# schematic.net
KiCad netlist of a schematic drawn in EasyEDA
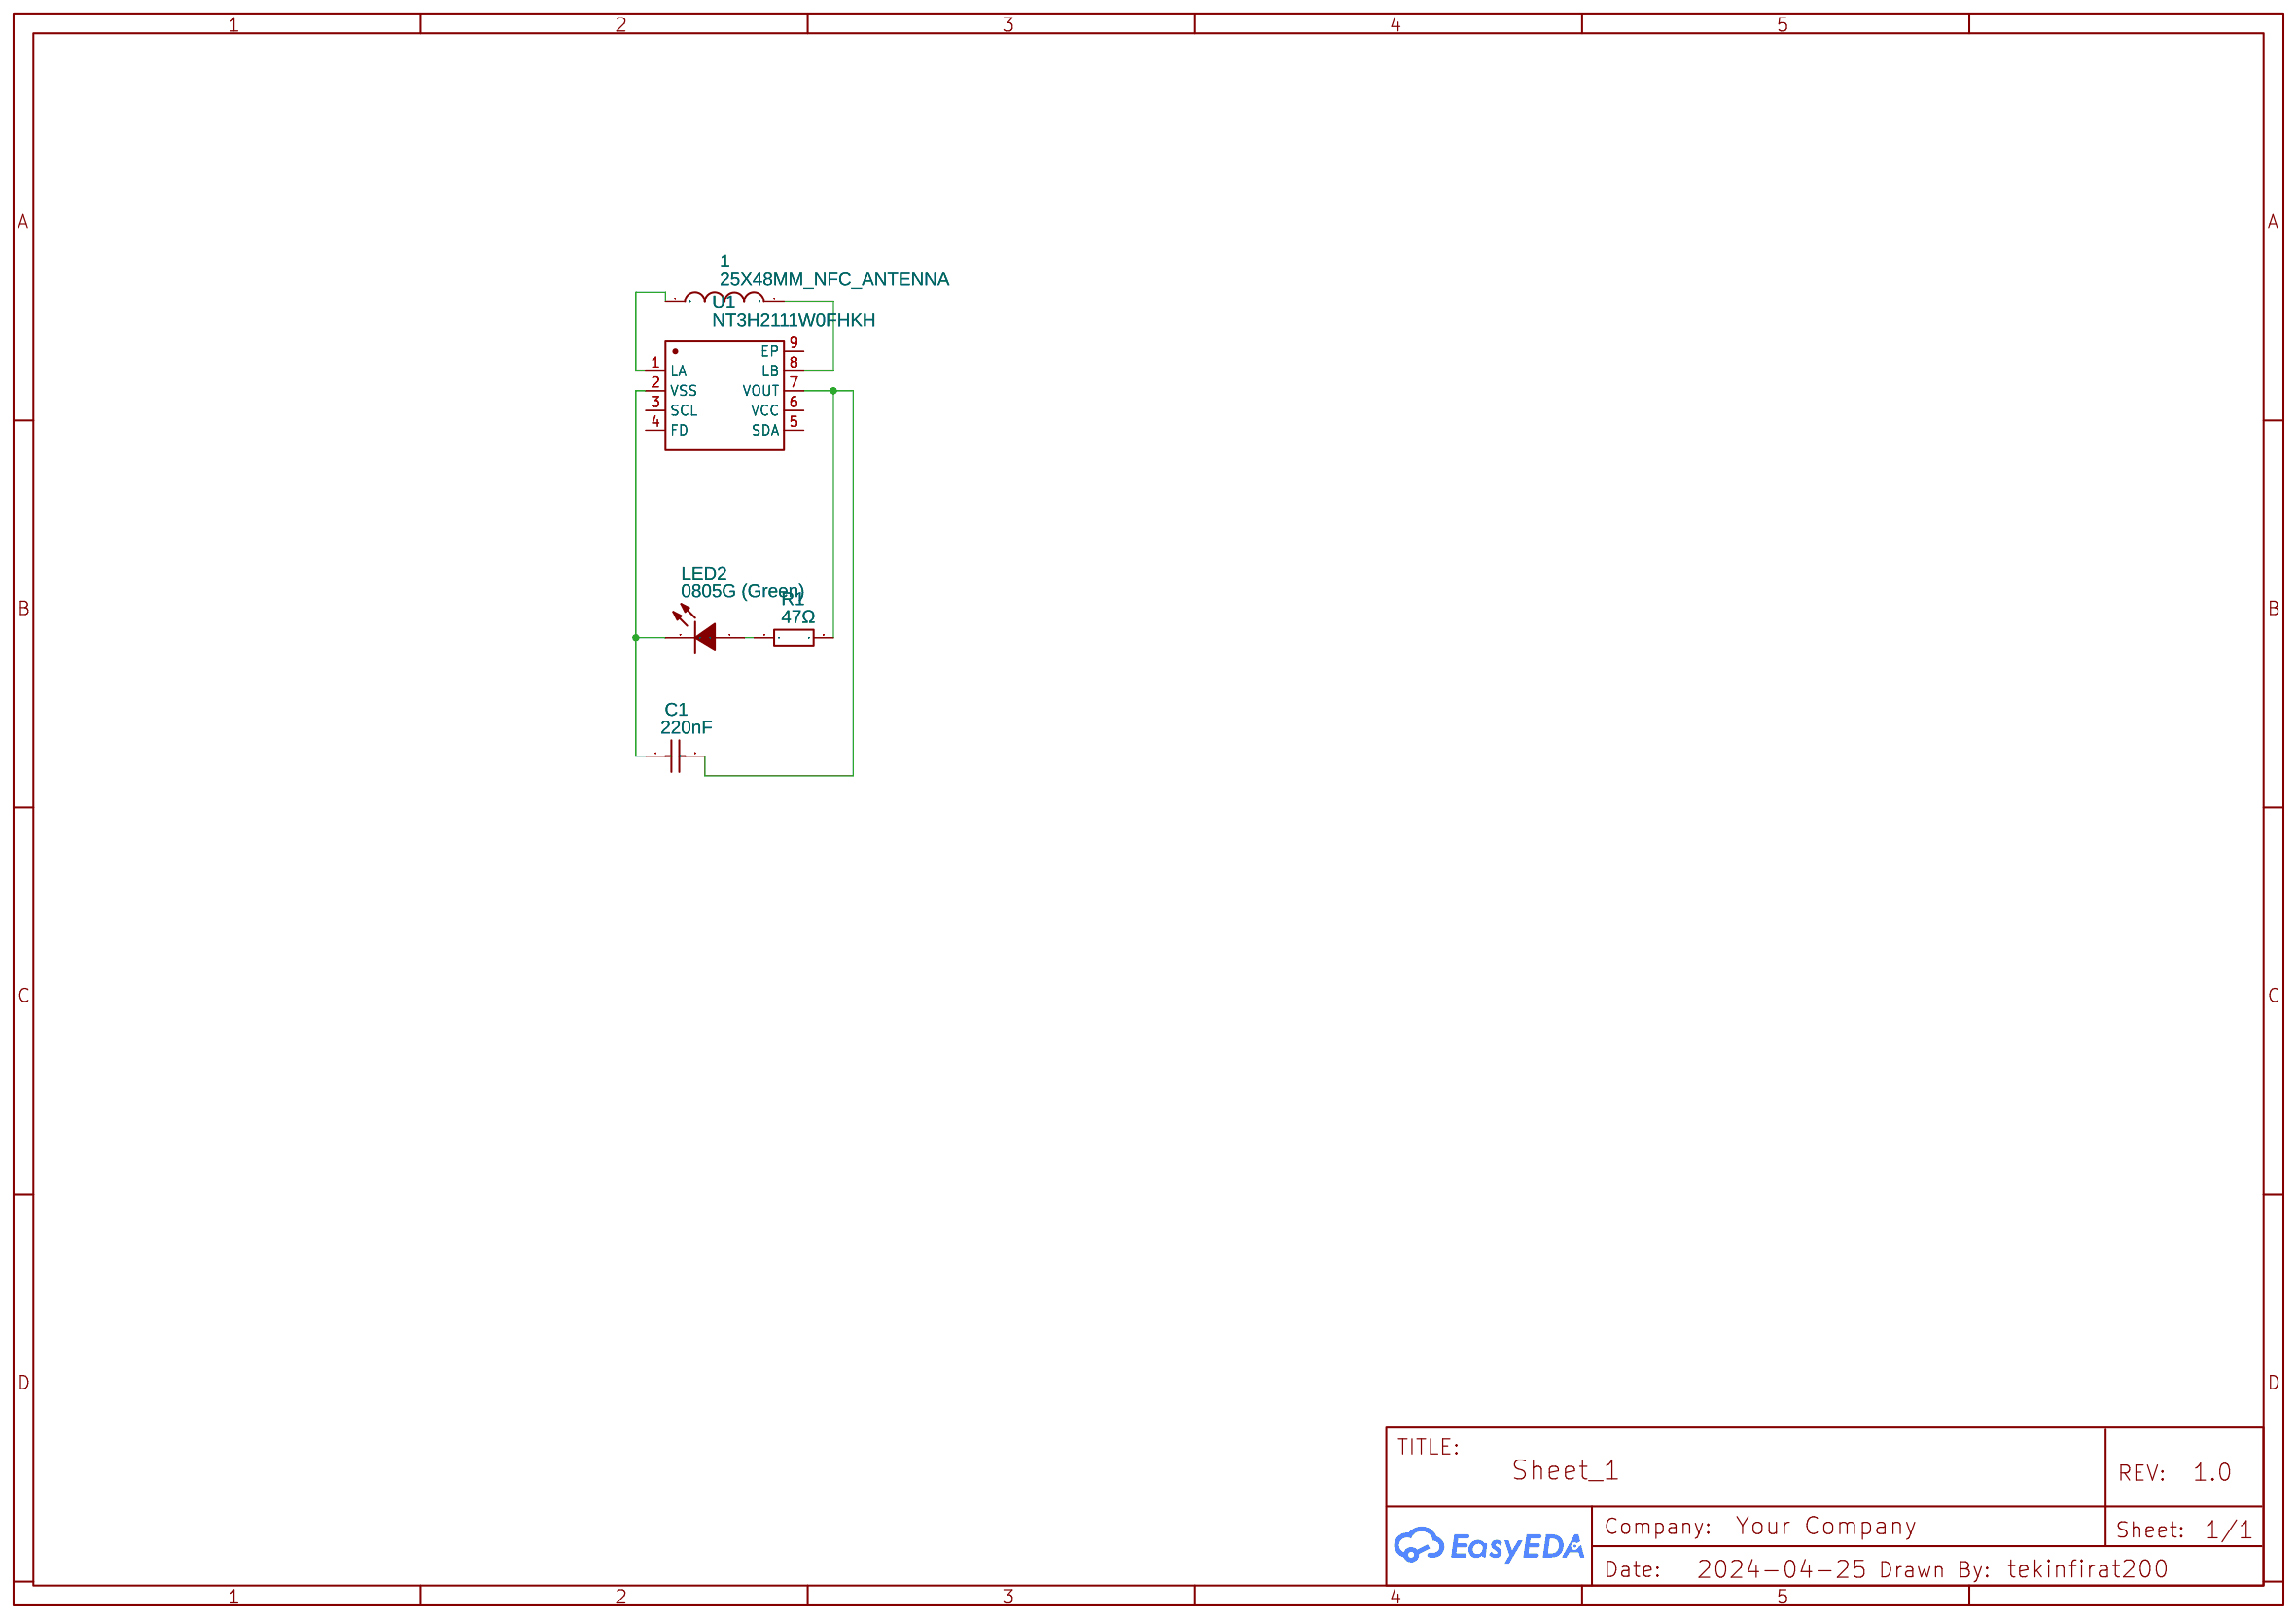
[diagram p0: schematic sheet]

(export (version "E")
  (design (tool "Eeschema 10.0.6"))
  (components
    (comp (ref "1") (value "25X48MM_NFC_ANTENNA") (libsource (lib "") (part "25X48MM_NFC_ANTENNA")))
    (comp (ref "C1")
      (value "220nF")
      (fields
        (field (name "Manufacturer Part") "CL10B224KA8NNNC")
        (field (name "Manufacturer") "SAMSUNG(三星)")
      )
      (libsource (lib "") (part "CL10B224KA8NNNC"))
    )
    (comp (ref "LED2")
      (value "0805G (Green)")
      (fields (field (name "Manufacturer Part") "KT-0805G") (field (name "Manufacturer") "KENTO"))
      (libsource (lib "") (part "0805G (Green)"))
    )
    (comp (ref "R1")
      (value "47Ω")
      (fields
        (field (name "Manufacturer Part") "0603WAF470JT5E")
        (field (name "Manufacturer") "UNI-ROYAL(厚声)")
      )
      (libsource (lib "") (part "0603WAF470JT5E"))
    )
    (comp (ref "U1")
      (value "NT3H2111W0FHKH")
      (fields (field (name "Manufacturer") "NXP(恩智浦)"))
      (libsource (lib "") (part "NT3H2111W0FHKH"))
    )
  )
  (nets
    (net (code "1") (name "Net-(LED2-A)") (class "Default")
      (node (ref "LED2") (pin "1") (pinfunction "A_1") (pintype "unspecified"))
      (node (ref "R1") (pin "1") (pinfunction "1_1") (pintype "input"))
    )
    (net (code "2") (name "Net-(LED2-K)") (class "Default")
      (node (ref "C1") (pin "1") (pinfunction "1_1") (pintype "input"))
      (node (ref "LED2") (pin "2") (pinfunction "K_2") (pintype "unspecified"))
      (node (ref "U1") (pin "2") (pinfunction "VSS_2") (pintype "unspecified"))
    )
    (net (code "3") (name "Net-(U1-LA)") (class "Default")
      (node (ref "1") (pin "P$1") (pinfunction "P$1_P$1") (pintype "bidirectional"))
      (node (ref "U1") (pin "1") (pinfunction "LA_1") (pintype "unspecified"))
    )
    (net (code "4") (name "Net-(U1-LB)") (class "Default")
      (node (ref "1") (pin "P$2") (pinfunction "P$2_P$2") (pintype "bidirectional"))
      (node (ref "U1") (pin "8") (pinfunction "LB_8") (pintype "unspecified"))
    )
    (net (code "5") (name "Net-(U1-VOUT)") (class "Default")
      (node (ref "C1") (pin "2") (pinfunction "2_2") (pintype "input"))
      (node (ref "R1") (pin "2") (pinfunction "2_2") (pintype "input"))
      (node (ref "U1") (pin "7") (pinfunction "VOUT_7") (pintype "unspecified"))
    )
    (net (code "6") (name "unconnected-(U1-EP-Pad9)") (class "Default")
      (node (ref "U1") (pin "9") (pinfunction "EP_9") (pintype "unspecified"))
    )
    (net (code "7") (name "unconnected-(U1-FD-Pad4)") (class "Default")
      (node (ref "U1") (pin "4") (pinfunction "FD_4") (pintype "unspecified"))
    )
    (net (code "8") (name "unconnected-(U1-SCL-Pad3)") (class "Default")
      (node (ref "U1") (pin "3") (pinfunction "SCL_3") (pintype "unspecified"))
    )
    (net (code "9") (name "unconnected-(U1-SDA-Pad5)") (class "Default")
      (node (ref "U1") (pin "5") (pinfunction "SDA_5") (pintype "unspecified"))
    )
    (net (code "10") (name "unconnected-(U1-VCC-Pad6)") (class "Default")
      (node (ref "U1") (pin "6") (pinfunction "VCC_6") (pintype "unspecified"))
    )
  )
)
